# EEG.net
KiCad netlist of a schematic drawn in EAGLE
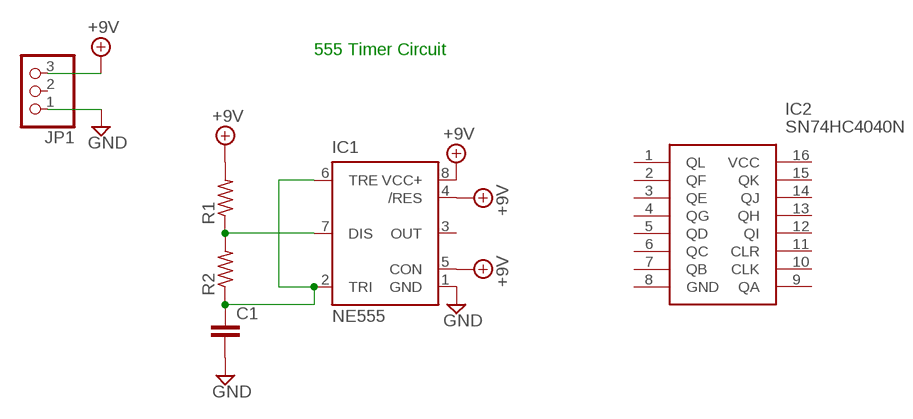
[diagram p0: schematic, sheet 1]

(export (version "E")
  (design (tool "Eeschema 10.0.6"))
  (components
    (comp (ref "C1")
      (value "C-EU050-025X075")
      (footprint "eagle-import:C050-025X075")
      (libsource (lib "eagle-import") (part "C-EU050-025X075"))
    )
    (comp (ref "IC1")
      (value "NE555")
      (footprint "eagle-import:DIL-08")
      (fields (field (name "MF") "Arrow Electronics") (field (name "MPN") "NE555N"))
      (libsource (lib "eagle-import") (part "NE555"))
    )
    (comp (ref "IC2")
      (value "SN74HC4040N")
      (footprint "eagle-import:DIP254P762X508-16")
      (fields (field (name "MOUSER_PART_NUMBER") "595-SN74HC4040N") (field (name "RS_PART_NUMBER") "0443255"))
      (libsource (lib "eagle-import") (part "SN74HC4040N"))
    )
    (comp (ref "JP1")
      (value "PINHD-1X3")
      (footprint "eagle-import:1X03")
      (libsource (lib "eagle-import") (part "PINHD-1X3"))
    )
    (comp (ref "R1")
      (value "R-US_0204/7")
      (footprint "eagle-import:0204_7")
      (libsource (lib "eagle-import") (part "R-US_0204/7"))
    )
    (comp (ref "R2")
      (value "R-US_0204/7")
      (footprint "eagle-import:0204_7")
      (libsource (lib "eagle-import") (part "R-US_0204/7"))
    )
  )
  (nets
    (net (code "1") (name "+9V") (class "Default")
      (node (ref "IC1") (pin "4") (pinfunction "/RES_4") (pintype "input"))
      (node (ref "IC1") (pin "5") (pinfunction "CON_5") (pintype "input"))
      (node (ref "IC1") (pin "8") (pinfunction "VCC+_8") (pintype "power_in"))
      (node (ref "JP1") (pin "3") (pinfunction "3_3") (pintype "passive"))
      (node (ref "R1") (pin "2") (pinfunction "2_2") (pintype "passive"))
    )
    (net (code "2") (name "GND") (class "Default")
      (node (ref "C1") (pin "2") (pinfunction "2_2") (pintype "passive"))
      (node (ref "IC1") (pin "1") (pinfunction "GND_1") (pintype "power_in"))
      (node (ref "JP1") (pin "1") (pinfunction "1_1") (pintype "passive"))
    )
    (net (code "3") (name "Net-(IC1-DIS)") (class "Default")
      (node (ref "IC1") (pin "7") (pinfunction "DIS_7") (pintype "input"))
      (node (ref "R1") (pin "1") (pinfunction "1_1") (pintype "passive"))
      (node (ref "R2") (pin "2") (pinfunction "2_2") (pintype "passive"))
    )
    (net (code "4") (name "Net-(IC1-TRE)") (class "Default")
      (node (ref "C1") (pin "1") (pinfunction "1_1") (pintype "passive"))
      (node (ref "IC1") (pin "2") (pinfunction "TRI_2") (pintype "input"))
      (node (ref "IC1") (pin "6") (pinfunction "TRE_6") (pintype "input"))
      (node (ref "R2") (pin "1") (pinfunction "1_1") (pintype "passive"))
    )
    (net (code "5") (name "unconnected-(IC1-OUT-Pad3)") (class "Default")
      (node (ref "IC1") (pin "3") (pinfunction "OUT_3") (pintype "output"))
    )
    (net (code "6") (name "unconnected-(IC2-CLK-Pad10)") (class "Default")
      (node (ref "IC2") (pin "10") (pinfunction "CLK_10") (pintype "bidirectional"))
    )
    (net (code "7") (name "unconnected-(IC2-CLR-Pad11)") (class "Default")
      (node (ref "IC2") (pin "11") (pinfunction "CLR_11") (pintype "bidirectional"))
    )
    (net (code "8") (name "unconnected-(IC2-GND-Pad8)") (class "Default")
      (node (ref "IC2") (pin "8") (pinfunction "GND_8") (pintype "bidirectional"))
    )
    (net (code "9") (name "unconnected-(IC2-QA-Pad9)") (class "Default")
      (node (ref "IC2") (pin "9") (pinfunction "QA_9") (pintype "bidirectional"))
    )
    (net (code "10") (name "unconnected-(IC2-QB-Pad7)") (class "Default")
      (node (ref "IC2") (pin "7") (pinfunction "QB_7") (pintype "bidirectional"))
    )
    (net (code "11") (name "unconnected-(IC2-QC-Pad6)") (class "Default")
      (node (ref "IC2") (pin "6") (pinfunction "QC_6") (pintype "bidirectional"))
    )
    (net (code "12") (name "unconnected-(IC2-QD-Pad5)") (class "Default")
      (node (ref "IC2") (pin "5") (pinfunction "QD_5") (pintype "bidirectional"))
    )
    (net (code "13") (name "unconnected-(IC2-QE-Pad3)") (class "Default")
      (node (ref "IC2") (pin "3") (pinfunction "QE_3") (pintype "bidirectional"))
    )
    (net (code "14") (name "unconnected-(IC2-QF-Pad2)") (class "Default")
      (node (ref "IC2") (pin "2") (pinfunction "QF_2") (pintype "bidirectional"))
    )
    (net (code "15") (name "unconnected-(IC2-QG-Pad4)") (class "Default")
      (node (ref "IC2") (pin "4") (pinfunction "QG_4") (pintype "bidirectional"))
    )
    (net (code "16") (name "unconnected-(IC2-QH-Pad13)") (class "Default")
      (node (ref "IC2") (pin "13") (pinfunction "QH_13") (pintype "bidirectional"))
    )
    (net (code "17") (name "unconnected-(IC2-QI-Pad12)") (class "Default")
      (node (ref "IC2") (pin "12") (pinfunction "QI_12") (pintype "bidirectional"))
    )
    (net (code "18") (name "unconnected-(IC2-QJ-Pad14)") (class "Default")
      (node (ref "IC2") (pin "14") (pinfunction "QJ_14") (pintype "bidirectional"))
    )
    (net (code "19") (name "unconnected-(IC2-QK-Pad15)") (class "Default")
      (node (ref "IC2") (pin "15") (pinfunction "QK_15") (pintype "bidirectional"))
    )
    (net (code "20") (name "unconnected-(IC2-QL-Pad1)") (class "Default")
      (node (ref "IC2") (pin "1") (pinfunction "QL_1") (pintype "bidirectional"))
    )
    (net (code "21") (name "unconnected-(IC2-VCC-Pad16)") (class "Default")
      (node (ref "IC2") (pin "16") (pinfunction "VCC_16") (pintype "bidirectional"))
    )
    (net (code "22") (name "unconnected-(JP1-Pad2)") (class "Default")
      (node (ref "JP1") (pin "2") (pinfunction "2_2") (pintype "passive"))
    )
  )
)
